# LightLinkV2.net
KiCad netlist of a schematic drawn in Altium Designer
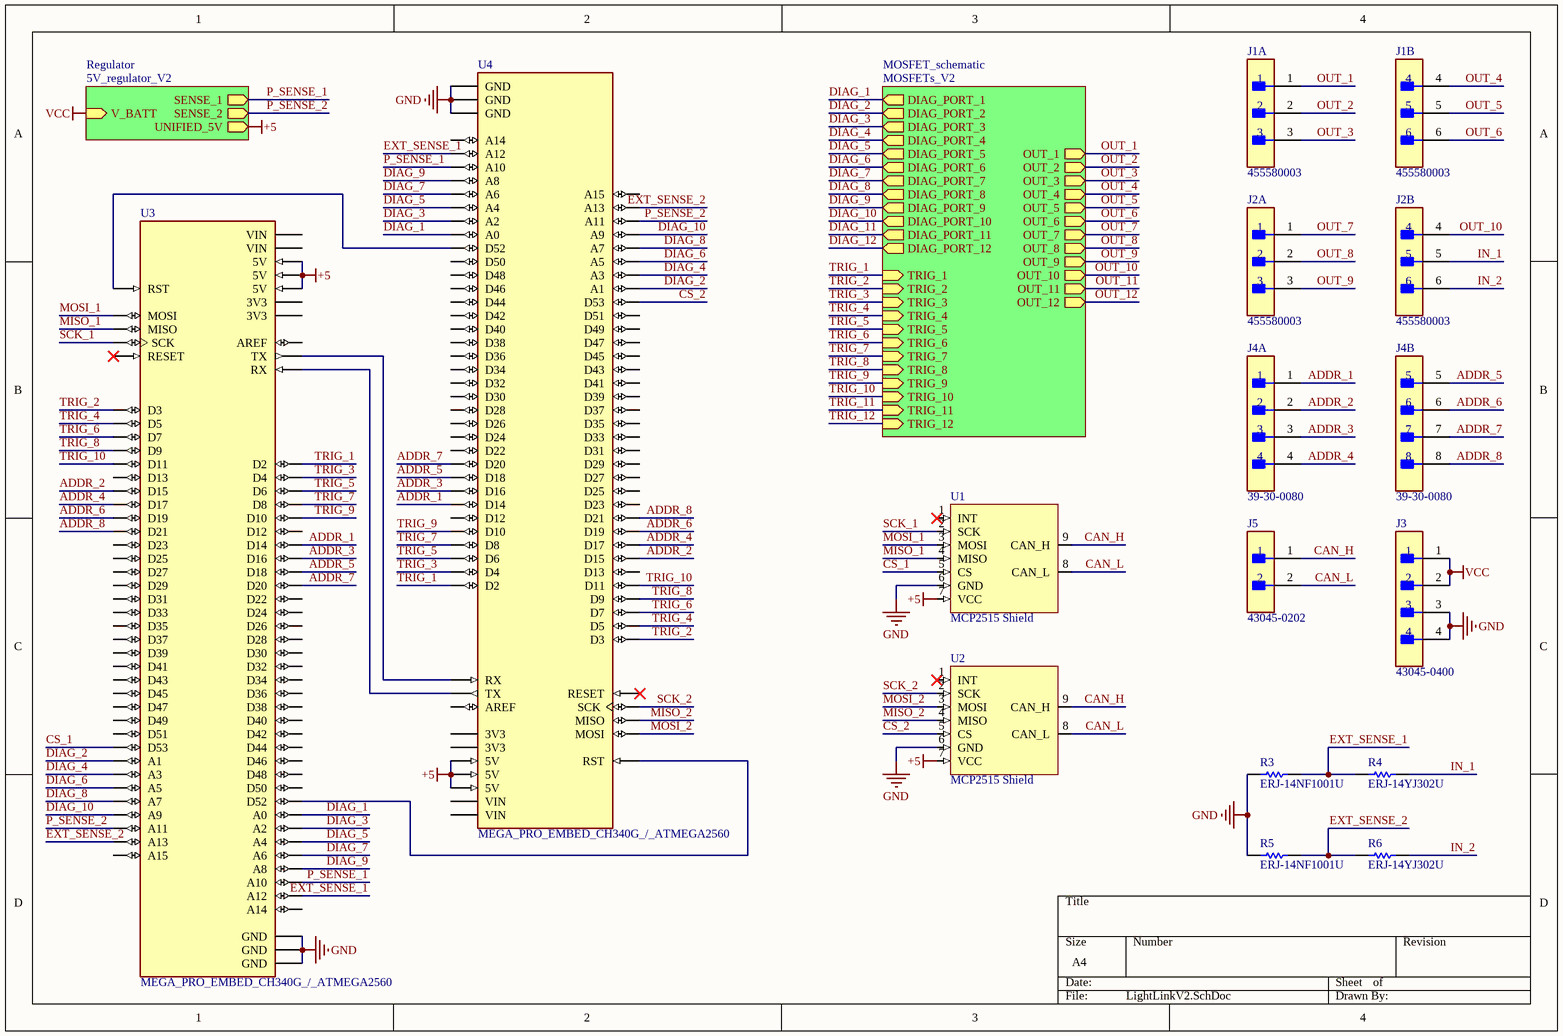
[diagram p0: LightLinkV2.SchDoc]

(export (version "E")
  (design (tool "Eeschema 10.0.6"))
  (components
    (comp (ref "J1")
      (value "455580003")
      (footprint "FP-455580003-MFG")
      (description "CONN HEADER R/A 6POS 4.2MM")
      (fields
        (field (name "OCTOPART") "https://octopart.com/45558-0003-molex-7672845")
        (field (name "MANUFACTURER") "Molex")
      )
      (libsource (lib "Altium Content Vault") (part "bb9cbdb24149a20ba329b4e86909569"))
    )
    (comp (ref "J2")
      (value "455580003")
      (footprint "FP-455580003-MFG")
      (description "CONN HEADER R/A 6POS 4.2MM")
      (fields
        (field (name "OCTOPART") "https://octopart.com/45558-0003-molex-7672845")
        (field (name "MANUFACTURER") "Molex")
      )
      (libsource (lib "Altium Content Vault") (part "bb9cbdb24149a20ba329b4e86909569"))
    )
    (comp (ref "J3")
      (value "43045-0400")
      (footprint "FP-43045-0400-MFG")
      (description "CONN HEADER R/A 4POS 3MM")
      (fields
        (field (name "MANUFACTURER") "Molex")
        (field (name "OCTOPART") "https://octopart.com/43045-0400-molex-287063")
      )
      (libsource (lib "Altium Content Vault") (part "c01754ab0efc13afb7424b896f394ef"))
    )
    (comp (ref "J4")
      (value "39-30-0080")
      (footprint "FP-39-30-0080-MFG")
      (description "CONN HEADER R/A 8POS 4.2MM")
      (libsource (lib "Altium Content Vault") (part "85438c39ca9ef07d43bb2e97c52bc44"))
    )
    (comp (ref "J5")
      (value "43045-0202")
      (footprint "FP-43045-0202-MFG")
      (description "CONN HEADER R/A 2POS")
      (libsource (lib "Altium Content Vault") (part "3bc925449376181038e59eaffc5286c"))
    )
    (comp (ref "R3")
      (value "ERJ-14NF1001U")
      (footprint "RESC3225X70X50NL20T20")
      (fields (field (name "MANUFACTURER") "Panasonic"))
      (libsource (lib "Altium Content Vault") (part "RES"))
    )
    (comp (ref "R4")
      (value "ERJ-14YJ302U")
      (footprint "RESC3225X70X50NL20T20")
      (fields (field (name "MANUFACTURER") "Panasonic"))
      (libsource (lib "Altium Content Vault") (part "RES"))
    )
    (comp (ref "R5")
      (value "ERJ-14NF1001U")
      (footprint "RESC3225X70X50NL20T20")
      (fields (field (name "MANUFACTURER") "Panasonic"))
      (libsource (lib "Altium Content Vault") (part "RES"))
    )
    (comp (ref "R6")
      (value "ERJ-14YJ302U")
      (footprint "RESC3225X70X50NL20T20")
      (fields (field (name "MANUFACTURER") "Panasonic"))
      (libsource (lib "Altium Content Vault") (part "RES"))
    )
    (comp (ref "U1")
      (value "MCP2515 Shield")
      (footprint "MCP2515 Shield-Footprint-1")
      (libsource (lib "uORocketry Hardware") (part "MCP2515 Shield Symbol"))
    )
    (comp (ref "U2")
      (value "MCP2515 Shield")
      (footprint "MCP2515 Shield-Footprint-1")
      (libsource (lib "uORocketry Hardware") (part "MCP2515 Shield Symbol"))
    )
    (comp (ref "U3")
      (value "MEGA_PRO_EMBED_CH340G_/_ATMEGA2560")
      (footprint "MODULE_MEGA_PRO_EMBED_CH340G_/_ATMEGA2560")
      (description "Mega 2560 PRO (Embed) CH340G/ATmega2560-16AU")
      (libsource (lib "") (part "MEGA_PRO_EMBED_CH340G_/_ATMEGA2560_1"))
    )
    (comp (ref "U4")
      (value "MEGA_PRO_EMBED_CH340G_/_ATMEGA2560")
      (footprint "MODULE_MEGA_PRO_EMBED_CH340G_/_ATMEGA2560")
      (description "Mega 2560 PRO (Embed) CH340G/ATmega2560-16AU")
      (libsource (lib "uORocketry Hardware") (part "MEGA_PRO_EMBED_CH340G_/_ATMEGA2560"))
    )
  )
  (nets
    (net (code "1") (name "+5") (class "Default")
      (node (ref "U1") (pin "7") (pinfunction "VCC_7") (pintype "input"))
      (node (ref "U2") (pin "7") (pinfunction "VCC_7") (pintype "input"))
      (node (ref "U3") (pin "5V_1") (pinfunction "5V_5V_1") (pintype "input"))
      (node (ref "U3") (pin "5V_2") (pinfunction "5V_5V_2") (pintype "input"))
      (node (ref "U3") (pin "5V_3") (pinfunction "5V_5V_3") (pintype "input"))
      (node (ref "U4") (pin "5V_1") (pinfunction "5V_5V_1") (pintype "input"))
      (node (ref "U4") (pin "5V_2") (pinfunction "5V_5V_2") (pintype "input"))
      (node (ref "U4") (pin "5V_3") (pinfunction "5V_5V_3") (pintype "input"))
    )
    (net (code "2") (name "/ADDR_1") (class "Default")
      (node (ref "J4") (pin "1") (pinfunction "1_1") (pintype "passive"))
      (node (ref "U3") (pin "D14") (pinfunction "D14_D14") (pintype "bidirectional"))
      (node (ref "U4") (pin "D14") (pinfunction "D14_D14") (pintype "bidirectional"))
    )
    (net (code "3") (name "/ADDR_2") (class "Default")
      (node (ref "J4") (pin "2") (pinfunction "2_2") (pintype "passive"))
      (node (ref "U3") (pin "D15") (pinfunction "D15_D15") (pintype "bidirectional"))
      (node (ref "U4") (pin "D15") (pinfunction "D15_D15") (pintype "bidirectional"))
    )
    (net (code "4") (name "/ADDR_3") (class "Default")
      (node (ref "J4") (pin "3") (pinfunction "3_3") (pintype "passive"))
      (node (ref "U3") (pin "D16") (pinfunction "D16_D16") (pintype "bidirectional"))
      (node (ref "U4") (pin "D16") (pinfunction "D16_D16") (pintype "bidirectional"))
    )
    (net (code "5") (name "/ADDR_4") (class "Default")
      (node (ref "J4") (pin "4") (pinfunction "4_4") (pintype "passive"))
      (node (ref "U3") (pin "D17") (pinfunction "D17_D17") (pintype "bidirectional"))
      (node (ref "U4") (pin "D17") (pinfunction "D17_D17") (pintype "bidirectional"))
    )
    (net (code "6") (name "/ADDR_5") (class "Default")
      (node (ref "J4") (pin "5") (pinfunction "5_5") (pintype "passive"))
      (node (ref "U3") (pin "D18") (pinfunction "D18_D18") (pintype "bidirectional"))
      (node (ref "U4") (pin "D18") (pinfunction "D18_D18") (pintype "bidirectional"))
    )
    (net (code "7") (name "/ADDR_6") (class "Default")
      (node (ref "J4") (pin "6") (pinfunction "6_6") (pintype "passive"))
      (node (ref "U3") (pin "D19") (pinfunction "D19_D19") (pintype "bidirectional"))
      (node (ref "U4") (pin "D19") (pinfunction "D19_D19") (pintype "bidirectional"))
    )
    (net (code "8") (name "/ADDR_7") (class "Default")
      (node (ref "J4") (pin "7") (pinfunction "7_7") (pintype "passive"))
      (node (ref "U3") (pin "D20") (pinfunction "D20_D20") (pintype "bidirectional"))
      (node (ref "U4") (pin "D20") (pinfunction "D20_D20") (pintype "bidirectional"))
    )
    (net (code "9") (name "/ADDR_8") (class "Default")
      (node (ref "J4") (pin "8") (pinfunction "8_8") (pintype "passive"))
      (node (ref "U3") (pin "D21") (pinfunction "D21_D21") (pintype "bidirectional"))
      (node (ref "U4") (pin "D21") (pinfunction "D21_D21") (pintype "bidirectional"))
    )
    (net (code "10") (name "/CAN_H") (class "Default")
      (node (ref "J5") (pin "1") (pinfunction "1_1") (pintype "passive"))
      (node (ref "U1") (pin "9") (pinfunction "CAN_H_9") (pintype "bidirectional"))
      (node (ref "U2") (pin "9") (pinfunction "CAN_H_9") (pintype "bidirectional"))
    )
    (net (code "11") (name "/CAN_L") (class "Default")
      (node (ref "J5") (pin "2") (pinfunction "2_2") (pintype "passive"))
      (node (ref "U1") (pin "8") (pinfunction "CAN_L_8") (pintype "bidirectional"))
      (node (ref "U2") (pin "8") (pinfunction "CAN_L_8") (pintype "bidirectional"))
    )
    (net (code "12") (name "/CS_1") (class "Default")
      (node (ref "U1") (pin "5") (pinfunction "CS_5") (pintype "input"))
      (node (ref "U3") (pin "D53") (pinfunction "D53_D53") (pintype "bidirectional"))
    )
    (net (code "13") (name "/CS_2") (class "Default")
      (node (ref "U2") (pin "5") (pinfunction "CS_5") (pintype "input"))
      (node (ref "U4") (pin "D53") (pinfunction "D53_D53") (pintype "bidirectional"))
    )
    (net (code "14") (name "/DIAG_1") (class "Default")
      (node (ref "U3") (pin "A0") (pinfunction "A0_A0") (pintype "bidirectional"))
      (node (ref "U4") (pin "A0") (pinfunction "A0_A0") (pintype "bidirectional"))
    )
    (net (code "15") (name "/DIAG_2") (class "Default")
      (node (ref "U3") (pin "A1") (pinfunction "A1_A1") (pintype "bidirectional"))
      (node (ref "U4") (pin "A1") (pinfunction "A1_A1") (pintype "bidirectional"))
    )
    (net (code "16") (name "/DIAG_3") (class "Default")
      (node (ref "U3") (pin "A2") (pinfunction "A2_A2") (pintype "bidirectional"))
      (node (ref "U4") (pin "A2") (pinfunction "A2_A2") (pintype "bidirectional"))
    )
    (net (code "17") (name "/DIAG_4") (class "Default")
      (node (ref "U3") (pin "A3") (pinfunction "A3_A3") (pintype "bidirectional"))
      (node (ref "U4") (pin "A3") (pinfunction "A3_A3") (pintype "bidirectional"))
    )
    (net (code "18") (name "/DIAG_5") (class "Default")
      (node (ref "U3") (pin "A4") (pinfunction "A4_A4") (pintype "bidirectional"))
      (node (ref "U4") (pin "A4") (pinfunction "A4_A4") (pintype "bidirectional"))
    )
    (net (code "19") (name "/DIAG_6") (class "Default")
      (node (ref "U3") (pin "A5") (pinfunction "A5_A5") (pintype "bidirectional"))
      (node (ref "U4") (pin "A5") (pinfunction "A5_A5") (pintype "bidirectional"))
    )
    (net (code "20") (name "/DIAG_7") (class "Default")
      (node (ref "U3") (pin "A6") (pinfunction "A6_A6") (pintype "bidirectional"))
      (node (ref "U4") (pin "A6") (pinfunction "A6_A6") (pintype "bidirectional"))
    )
    (net (code "21") (name "/DIAG_8") (class "Default")
      (node (ref "U3") (pin "A7") (pinfunction "A7_A7") (pintype "bidirectional"))
      (node (ref "U4") (pin "A7") (pinfunction "A7_A7") (pintype "bidirectional"))
    )
    (net (code "22") (name "/DIAG_9") (class "Default")
      (node (ref "U3") (pin "A8") (pinfunction "A8_A8") (pintype "bidirectional"))
      (node (ref "U4") (pin "A8") (pinfunction "A8_A8") (pintype "bidirectional"))
    )
    (net (code "23") (name "/DIAG_10") (class "Default")
      (node (ref "U3") (pin "A9") (pinfunction "A9_A9") (pintype "bidirectional"))
      (node (ref "U4") (pin "A9") (pinfunction "A9_A9") (pintype "bidirectional"))
    )
    (net (code "26") (name "/EXT_SENSE_1") (class "Default")
      (node (ref "R3") (pin "2") (pinfunction "2_2") (pintype "passive"))
      (node (ref "R4") (pin "1") (pinfunction "1_1") (pintype "passive"))
      (node (ref "U3") (pin "A12") (pinfunction "A12_A12") (pintype "bidirectional"))
      (node (ref "U4") (pin "A12") (pinfunction "A12_A12") (pintype "bidirectional"))
    )
    (net (code "27") (name "/EXT_SENSE_2") (class "Default")
      (node (ref "R5") (pin "2") (pinfunction "2_2") (pintype "passive"))
      (node (ref "R6") (pin "1") (pinfunction "1_1") (pintype "passive"))
      (node (ref "U3") (pin "A13") (pinfunction "A13_A13") (pintype "bidirectional"))
      (node (ref "U4") (pin "A13") (pinfunction "A13_A13") (pintype "bidirectional"))
    )
    (net (code "28") (name "/IN_1") (class "Default")
      (node (ref "J2") (pin "5") (pinfunction "5_5") (pintype "passive"))
      (node (ref "R4") (pin "2") (pinfunction "2_2") (pintype "passive"))
    )
    (net (code "29") (name "/IN_2") (class "Default")
      (node (ref "J2") (pin "6") (pinfunction "6_6") (pintype "passive"))
      (node (ref "R6") (pin "2") (pinfunction "2_2") (pintype "passive"))
    )
    (net (code "30") (name "/MISO_1") (class "Default")
      (node (ref "U1") (pin "4") (pinfunction "MISO_4") (pintype "input"))
      (node (ref "U3") (pin "MISO") (pinfunction "MISO_MISO") (pintype "bidirectional"))
    )
    (net (code "31") (name "/MISO_2") (class "Default")
      (node (ref "U2") (pin "4") (pinfunction "MISO_4") (pintype "input"))
      (node (ref "U4") (pin "MISO") (pinfunction "MISO_MISO") (pintype "bidirectional"))
    )
    (net (code "32") (name "/MOSI_1") (class "Default")
      (node (ref "U1") (pin "3") (pinfunction "MOSI_3") (pintype "input"))
      (node (ref "U3") (pin "MOSI") (pinfunction "MOSI_MOSI") (pintype "bidirectional"))
    )
    (net (code "33") (name "/MOSI_2") (class "Default")
      (node (ref "U2") (pin "3") (pinfunction "MOSI_3") (pintype "input"))
      (node (ref "U4") (pin "MOSI") (pinfunction "MOSI_MOSI") (pintype "bidirectional"))
    )
    (net (code "34") (name "/OUT_1") (class "Default")
      (node (ref "J1") (pin "1") (pinfunction "1_1") (pintype "passive"))
    )
    (net (code "35") (name "/OUT_2") (class "Default")
      (node (ref "J1") (pin "2") (pinfunction "2_2") (pintype "passive"))
    )
    (net (code "36") (name "/OUT_3") (class "Default")
      (node (ref "J1") (pin "3") (pinfunction "3_3") (pintype "passive"))
    )
    (net (code "37") (name "/OUT_4") (class "Default")
      (node (ref "J1") (pin "4") (pinfunction "4_4") (pintype "passive"))
    )
    (net (code "38") (name "/OUT_5") (class "Default")
      (node (ref "J1") (pin "5") (pinfunction "5_5") (pintype "passive"))
    )
    (net (code "39") (name "/OUT_6") (class "Default")
      (node (ref "J1") (pin "6") (pinfunction "6_6") (pintype "passive"))
    )
    (net (code "40") (name "/OUT_7") (class "Default")
      (node (ref "J2") (pin "1") (pinfunction "1_1") (pintype "passive"))
    )
    (net (code "41") (name "/OUT_8") (class "Default")
      (node (ref "J2") (pin "2") (pinfunction "2_2") (pintype "passive"))
    )
    (net (code "42") (name "/OUT_9") (class "Default")
      (node (ref "J2") (pin "3") (pinfunction "3_3") (pintype "passive"))
    )
    (net (code "43") (name "/OUT_10") (class "Default")
      (node (ref "J2") (pin "4") (pinfunction "4_4") (pintype "passive"))
    )
    (net (code "46") (name "/P_SENSE_1") (class "Default")
      (node (ref "U3") (pin "A10") (pinfunction "A10_A10") (pintype "bidirectional"))
      (node (ref "U4") (pin "A10") (pinfunction "A10_A10") (pintype "bidirectional"))
    )
    (net (code "47") (name "/P_SENSE_2") (class "Default")
      (node (ref "U3") (pin "A11") (pinfunction "A11_A11") (pintype "bidirectional"))
      (node (ref "U4") (pin "A11") (pinfunction "A11_A11") (pintype "bidirectional"))
    )
    (net (code "48") (name "/SCK_1") (class "Default")
      (node (ref "U1") (pin "2") (pinfunction "SCK_2") (pintype "input"))
      (node (ref "U3") (pin "SCK") (pinfunction "SCK_SCK") (pintype "bidirectional"))
    )
    (net (code "49") (name "/SCK_2") (class "Default")
      (node (ref "U2") (pin "2") (pinfunction "SCK_2") (pintype "input"))
      (node (ref "U4") (pin "SCK") (pinfunction "SCK_SCK") (pintype "bidirectional"))
    )
    (net (code "50") (name "/TRIG_1") (class "Default")
      (node (ref "U3") (pin "D2") (pinfunction "D2_D2") (pintype "bidirectional"))
      (node (ref "U4") (pin "D2") (pinfunction "D2_D2") (pintype "bidirectional"))
    )
    (net (code "51") (name "/TRIG_2") (class "Default")
      (node (ref "U3") (pin "D3") (pinfunction "D3_D3") (pintype "bidirectional"))
      (node (ref "U4") (pin "D3") (pinfunction "D3_D3") (pintype "bidirectional"))
    )
    (net (code "52") (name "/TRIG_3") (class "Default")
      (node (ref "U3") (pin "D4") (pinfunction "D4_D4") (pintype "bidirectional"))
      (node (ref "U4") (pin "D4") (pinfunction "D4_D4") (pintype "bidirectional"))
    )
    (net (code "53") (name "/TRIG_4") (class "Default")
      (node (ref "U3") (pin "D5") (pinfunction "D5_D5") (pintype "bidirectional"))
      (node (ref "U4") (pin "D5") (pinfunction "D5_D5") (pintype "bidirectional"))
    )
    (net (code "54") (name "/TRIG_5") (class "Default")
      (node (ref "U3") (pin "D6") (pinfunction "D6_D6") (pintype "bidirectional"))
      (node (ref "U4") (pin "D6") (pinfunction "D6_D6") (pintype "bidirectional"))
    )
    (net (code "55") (name "/TRIG_6") (class "Default")
      (node (ref "U3") (pin "D7") (pinfunction "D7_D7") (pintype "bidirectional"))
      (node (ref "U4") (pin "D7") (pinfunction "D7_D7") (pintype "bidirectional"))
    )
    (net (code "56") (name "/TRIG_7") (class "Default")
      (node (ref "U3") (pin "D8") (pinfunction "D8_D8") (pintype "bidirectional"))
      (node (ref "U4") (pin "D8") (pinfunction "D8_D8") (pintype "bidirectional"))
    )
    (net (code "57") (name "/TRIG_8") (class "Default")
      (node (ref "U3") (pin "D9") (pinfunction "D9_D9") (pintype "bidirectional"))
      (node (ref "U4") (pin "D9") (pinfunction "D9_D9") (pintype "bidirectional"))
    )
    (net (code "58") (name "/TRIG_9") (class "Default")
      (node (ref "U3") (pin "D10") (pinfunction "D10_D10") (pintype "bidirectional"))
      (node (ref "U4") (pin "D10") (pinfunction "D10_D10") (pintype "bidirectional"))
    )
    (net (code "59") (name "/TRIG_10") (class "Default")
      (node (ref "U3") (pin "D11") (pinfunction "D11_D11") (pintype "bidirectional"))
      (node (ref "U4") (pin "D11") (pinfunction "D11_D11") (pintype "bidirectional"))
    )
    (net (code "62") (name "GND") (class "Default")
      (node (ref "J3") (pin "3") (pinfunction "3_3") (pintype "passive"))
      (node (ref "J3") (pin "4") (pinfunction "4_4") (pintype "passive"))
      (node (ref "R3") (pin "1") (pinfunction "1_1") (pintype "passive"))
      (node (ref "R5") (pin "1") (pinfunction "1_1") (pintype "passive"))
      (node (ref "U1") (pin "6") (pinfunction "GND_6") (pintype "input"))
      (node (ref "U2") (pin "6") (pinfunction "GND_6") (pintype "input"))
      (node (ref "U3") (pin "GND_1") (pinfunction "GND_GND_1") (pintype "power_in"))
      (node (ref "U3") (pin "GND_2") (pinfunction "GND_GND_2") (pintype "power_in"))
      (node (ref "U3") (pin "GND_3") (pinfunction "GND_GND_3") (pintype "power_in"))
      (node (ref "U4") (pin "GND_1") (pinfunction "GND_GND_1") (pintype "power_in"))
      (node (ref "U4") (pin "GND_2") (pinfunction "GND_GND_2") (pintype "power_in"))
      (node (ref "U4") (pin "GND_3") (pinfunction "GND_GND_3") (pintype "power_in"))
    )
    (net (code "63") (name "Net-(U3-PadD52)") (class "Default")
      (node (ref "U3") (pin "D52") (pinfunction "D52_D52") (pintype "bidirectional"))
      (node (ref "U4") (pin "RST") (pinfunction "RST_RST") (pintype "input"))
    )
    (net (code "64") (name "Net-(U3-PadRST)") (class "Default")
      (node (ref "U3") (pin "RST") (pinfunction "RST_RST") (pintype "input"))
      (node (ref "U4") (pin "D52") (pinfunction "D52_D52") (pintype "bidirectional"))
    )
    (net (code "65") (name "Net-(U3-PadRX)") (class "Default")
      (node (ref "U3") (pin "RX") (pinfunction "RX_RX") (pintype "input"))
      (node (ref "U4") (pin "TX") (pinfunction "TX_TX") (pintype "output"))
    )
    (net (code "66") (name "Net-(U3-PadTX)") (class "Default")
      (node (ref "U3") (pin "TX") (pinfunction "TX_TX") (pintype "output"))
      (node (ref "U4") (pin "RX") (pinfunction "RX_RX") (pintype "input"))
    )
    (net (code "67") (name "VCC") (class "Default")
      (node (ref "J3") (pin "1") (pinfunction "1_1") (pintype "passive"))
      (node (ref "J3") (pin "2") (pinfunction "2_2") (pintype "passive"))
    )
    (net (code "68") (name "unconnected-(U1-INT-Pad1)") (class "Default")
      (node (ref "U1") (pin "1") (pinfunction "INT_1") (pintype "input+no_connect"))
    )
    (net (code "69") (name "unconnected-(U2-INT-Pad1)") (class "Default")
      (node (ref "U2") (pin "1") (pinfunction "INT_1") (pintype "input+no_connect"))
    )
    (net (code "70") (name "unconnected-(U3-3V3-Pad3V3_1)") (class "Default")
      (node (ref "U3") (pin "3V3_1") (pinfunction "3V3_3V3_1") (pintype "power_in"))
    )
    (net (code "71") (name "unconnected-(U3-3V3-Pad3V3_2)") (class "Default")
      (node (ref "U3") (pin "3V3_2") (pinfunction "3V3_3V3_2") (pintype "power_in"))
    )
    (net (code "72") (name "unconnected-(U3-PadA14)") (class "Default")
      (node (ref "U3") (pin "A14") (pinfunction "A14_A14") (pintype "bidirectional"))
    )
    (net (code "73") (name "unconnected-(U3-PadA15)") (class "Default")
      (node (ref "U3") (pin "A15") (pinfunction "A15_A15") (pintype "bidirectional"))
    )
    (net (code "74") (name "unconnected-(U3-PadAREF)") (class "Default")
      (node (ref "U3") (pin "AREF") (pinfunction "AREF_AREF") (pintype "bidirectional"))
    )
    (net (code "75") (name "unconnected-(U3-PadD12)") (class "Default")
      (node (ref "U3") (pin "D12") (pinfunction "D12_D12") (pintype "bidirectional"))
    )
    (net (code "76") (name "unconnected-(U3-PadD13)") (class "Default")
      (node (ref "U3") (pin "D13") (pinfunction "D13_D13") (pintype "bidirectional"))
    )
    (net (code "77") (name "unconnected-(U3-PadD22)") (class "Default")
      (node (ref "U3") (pin "D22") (pinfunction "D22_D22") (pintype "bidirectional"))
    )
    (net (code "78") (name "unconnected-(U3-PadD23)") (class "Default")
      (node (ref "U3") (pin "D23") (pinfunction "D23_D23") (pintype "bidirectional"))
    )
    (net (code "79") (name "unconnected-(U3-PadD24)") (class "Default")
      (node (ref "U3") (pin "D24") (pinfunction "D24_D24") (pintype "bidirectional"))
    )
    (net (code "80") (name "unconnected-(U3-PadD25)") (class "Default")
      (node (ref "U3") (pin "D25") (pinfunction "D25_D25") (pintype "bidirectional"))
    )
    (net (code "81") (name "unconnected-(U3-PadD26)") (class "Default")
      (node (ref "U3") (pin "D26") (pinfunction "D26_D26") (pintype "bidirectional"))
    )
    (net (code "82") (name "unconnected-(U3-PadD27)") (class "Default")
      (node (ref "U3") (pin "D27") (pinfunction "D27_D27") (pintype "bidirectional"))
    )
    (net (code "83") (name "unconnected-(U3-PadD28)") (class "Default")
      (node (ref "U3") (pin "D28") (pinfunction "D28_D28") (pintype "bidirectional"))
    )
    (net (code "84") (name "unconnected-(U3-PadD29)") (class "Default")
      (node (ref "U3") (pin "D29") (pinfunction "D29_D29") (pintype "bidirectional"))
    )
    (net (code "85") (name "unconnected-(U3-PadD30)") (class "Default")
      (node (ref "U3") (pin "D30") (pinfunction "D30_D30") (pintype "bidirectional"))
    )
    (net (code "86") (name "unconnected-(U3-PadD31)") (class "Default")
      (node (ref "U3") (pin "D31") (pinfunction "D31_D31") (pintype "bidirectional"))
    )
    (net (code "87") (name "unconnected-(U3-PadD32)") (class "Default")
      (node (ref "U3") (pin "D32") (pinfunction "D32_D32") (pintype "bidirectional"))
    )
    (net (code "88") (name "unconnected-(U3-PadD33)") (class "Default")
      (node (ref "U3") (pin "D33") (pinfunction "D33_D33") (pintype "bidirectional"))
    )
    (net (code "89") (name "unconnected-(U3-PadD34)") (class "Default")
      (node (ref "U3") (pin "D34") (pinfunction "D34_D34") (pintype "bidirectional"))
    )
    (net (code "90") (name "unconnected-(U3-PadD35)") (class "Default")
      (node (ref "U3") (pin "D35") (pinfunction "D35_D35") (pintype "bidirectional"))
    )
    (net (code "91") (name "unconnected-(U3-PadD36)") (class "Default")
      (node (ref "U3") (pin "D36") (pinfunction "D36_D36") (pintype "bidirectional"))
    )
    (net (code "92") (name "unconnected-(U3-PadD37)") (class "Default")
      (node (ref "U3") (pin "D37") (pinfunction "D37_D37") (pintype "bidirectional"))
    )
    (net (code "93") (name "unconnected-(U3-PadD38)") (class "Default")
      (node (ref "U3") (pin "D38") (pinfunction "D38_D38") (pintype "bidirectional"))
    )
    (net (code "94") (name "unconnected-(U3-PadD39)") (class "Default")
      (node (ref "U3") (pin "D39") (pinfunction "D39_D39") (pintype "bidirectional"))
    )
    (net (code "95") (name "unconnected-(U3-PadD40)") (class "Default")
      (node (ref "U3") (pin "D40") (pinfunction "D40_D40") (pintype "bidirectional"))
    )
    (net (code "96") (name "unconnected-(U3-PadD41)") (class "Default")
      (node (ref "U3") (pin "D41") (pinfunction "D41_D41") (pintype "bidirectional"))
    )
    (net (code "97") (name "unconnected-(U3-PadD42)") (class "Default")
      (node (ref "U3") (pin "D42") (pinfunction "D42_D42") (pintype "bidirectional"))
    )
    (net (code "98") (name "unconnected-(U3-PadD43)") (class "Default")
      (node (ref "U3") (pin "D43") (pinfunction "D43_D43") (pintype "bidirectional"))
    )
    (net (code "99") (name "unconnected-(U3-PadD44)") (class "Default")
      (node (ref "U3") (pin "D44") (pinfunction "D44_D44") (pintype "bidirectional"))
    )
    (net (code "100") (name "unconnected-(U3-PadD45)") (class "Default")
      (node (ref "U3") (pin "D45") (pinfunction "D45_D45") (pintype "bidirectional"))
    )
    (net (code "101") (name "unconnected-(U3-PadD46)") (class "Default")
      (node (ref "U3") (pin "D46") (pinfunction "D46_D46") (pintype "bidirectional"))
    )
    (net (code "102") (name "unconnected-(U3-PadD47)") (class "Default")
      (node (ref "U3") (pin "D47") (pinfunction "D47_D47") (pintype "bidirectional"))
    )
    (net (code "103") (name "unconnected-(U3-PadD48)") (class "Default")
      (node (ref "U3") (pin "D48") (pinfunction "D48_D48") (pintype "bidirectional"))
    )
    (net (code "104") (name "unconnected-(U3-PadD49)") (class "Default")
      (node (ref "U3") (pin "D49") (pinfunction "D49_D49") (pintype "bidirectional"))
    )
    (net (code "105") (name "unconnected-(U3-PadD50)") (class "Default")
      (node (ref "U3") (pin "D50") (pinfunction "D50_D50") (pintype "bidirectional"))
    )
    (net (code "106") (name "unconnected-(U3-PadD51)") (class "Default")
      (node (ref "U3") (pin "D51") (pinfunction "D51_D51") (pintype "bidirectional"))
    )
    (net (code "107") (name "unconnected-(U3-PadRESET)") (class "Default")
      (node (ref "U3") (pin "RESET") (pinfunction "RESET_RESET") (pintype "input+no_connect"))
    )
    (net (code "108") (name "unconnected-(U3-VIN-PadVIN_1)") (class "Default")
      (node (ref "U3") (pin "VIN_1") (pinfunction "VIN_VIN_1") (pintype "power_in"))
    )
    (net (code "109") (name "unconnected-(U3-VIN-PadVIN_2)") (class "Default")
      (node (ref "U3") (pin "VIN_2") (pinfunction "VIN_VIN_2") (pintype "power_in"))
    )
    (net (code "110") (name "unconnected-(U4-3V3-Pad3V3_1)") (class "Default")
      (node (ref "U4") (pin "3V3_1") (pinfunction "3V3_3V3_1") (pintype "power_in"))
    )
    (net (code "111") (name "unconnected-(U4-3V3-Pad3V3_2)") (class "Default")
      (node (ref "U4") (pin "3V3_2") (pinfunction "3V3_3V3_2") (pintype "power_in"))
    )
    (net (code "112") (name "unconnected-(U4-PadA14)") (class "Default")
      (node (ref "U4") (pin "A14") (pinfunction "A14_A14") (pintype "bidirectional"))
    )
    (net (code "113") (name "unconnected-(U4-PadA15)") (class "Default")
      (node (ref "U4") (pin "A15") (pinfunction "A15_A15") (pintype "bidirectional"))
    )
    (net (code "114") (name "unconnected-(U4-PadAREF)") (class "Default")
      (node (ref "U4") (pin "AREF") (pinfunction "AREF_AREF") (pintype "bidirectional"))
    )
    (net (code "115") (name "unconnected-(U4-PadD12)") (class "Default")
      (node (ref "U4") (pin "D12") (pinfunction "D12_D12") (pintype "bidirectional"))
    )
    (net (code "116") (name "unconnected-(U4-PadD13)") (class "Default")
      (node (ref "U4") (pin "D13") (pinfunction "D13_D13") (pintype "bidirectional"))
    )
    (net (code "117") (name "unconnected-(U4-PadD22)") (class "Default")
      (node (ref "U4") (pin "D22") (pinfunction "D22_D22") (pintype "bidirectional"))
    )
    (net (code "118") (name "unconnected-(U4-PadD23)") (class "Default")
      (node (ref "U4") (pin "D23") (pinfunction "D23_D23") (pintype "bidirectional"))
    )
    (net (code "119") (name "unconnected-(U4-PadD24)") (class "Default")
      (node (ref "U4") (pin "D24") (pinfunction "D24_D24") (pintype "bidirectional"))
    )
    (net (code "120") (name "unconnected-(U4-PadD25)") (class "Default")
      (node (ref "U4") (pin "D25") (pinfunction "D25_D25") (pintype "bidirectional"))
    )
    (net (code "121") (name "unconnected-(U4-PadD26)") (class "Default")
      (node (ref "U4") (pin "D26") (pinfunction "D26_D26") (pintype "bidirectional"))
    )
    (net (code "122") (name "unconnected-(U4-PadD27)") (class "Default")
      (node (ref "U4") (pin "D27") (pinfunction "D27_D27") (pintype "bidirectional"))
    )
    (net (code "123") (name "unconnected-(U4-PadD28)") (class "Default")
      (node (ref "U4") (pin "D28") (pinfunction "D28_D28") (pintype "bidirectional"))
    )
    (net (code "124") (name "unconnected-(U4-PadD29)") (class "Default")
      (node (ref "U4") (pin "D29") (pinfunction "D29_D29") (pintype "bidirectional"))
    )
    (net (code "125") (name "unconnected-(U4-PadD30)") (class "Default")
      (node (ref "U4") (pin "D30") (pinfunction "D30_D30") (pintype "bidirectional"))
    )
    (net (code "126") (name "unconnected-(U4-PadD31)") (class "Default")
      (node (ref "U4") (pin "D31") (pinfunction "D31_D31") (pintype "bidirectional"))
    )
    (net (code "127") (name "unconnected-(U4-PadD32)") (class "Default")
      (node (ref "U4") (pin "D32") (pinfunction "D32_D32") (pintype "bidirectional"))
    )
    (net (code "128") (name "unconnected-(U4-PadD33)") (class "Default")
      (node (ref "U4") (pin "D33") (pinfunction "D33_D33") (pintype "bidirectional"))
    )
    (net (code "129") (name "unconnected-(U4-PadD34)") (class "Default")
      (node (ref "U4") (pin "D34") (pinfunction "D34_D34") (pintype "bidirectional"))
    )
    (net (code "130") (name "unconnected-(U4-PadD35)") (class "Default")
      (node (ref "U4") (pin "D35") (pinfunction "D35_D35") (pintype "bidirectional"))
    )
    (net (code "131") (name "unconnected-(U4-PadD36)") (class "Default")
      (node (ref "U4") (pin "D36") (pinfunction "D36_D36") (pintype "bidirectional"))
    )
    (net (code "132") (name "unconnected-(U4-PadD37)") (class "Default")
      (node (ref "U4") (pin "D37") (pinfunction "D37_D37") (pintype "bidirectional"))
    )
    (net (code "133") (name "unconnected-(U4-PadD38)") (class "Default")
      (node (ref "U4") (pin "D38") (pinfunction "D38_D38") (pintype "bidirectional"))
    )
    (net (code "134") (name "unconnected-(U4-PadD39)") (class "Default")
      (node (ref "U4") (pin "D39") (pinfunction "D39_D39") (pintype "bidirectional"))
    )
    (net (code "135") (name "unconnected-(U4-PadD40)") (class "Default")
      (node (ref "U4") (pin "D40") (pinfunction "D40_D40") (pintype "bidirectional"))
    )
    (net (code "136") (name "unconnected-(U4-PadD41)") (class "Default")
      (node (ref "U4") (pin "D41") (pinfunction "D41_D41") (pintype "bidirectional"))
    )
    (net (code "137") (name "unconnected-(U4-PadD42)") (class "Default")
      (node (ref "U4") (pin "D42") (pinfunction "D42_D42") (pintype "bidirectional"))
    )
    (net (code "138") (name "unconnected-(U4-PadD43)") (class "Default")
      (node (ref "U4") (pin "D43") (pinfunction "D43_D43") (pintype "bidirectional"))
    )
    (net (code "139") (name "unconnected-(U4-PadD44)") (class "Default")
      (node (ref "U4") (pin "D44") (pinfunction "D44_D44") (pintype "bidirectional"))
    )
    (net (code "140") (name "unconnected-(U4-PadD45)") (class "Default")
      (node (ref "U4") (pin "D45") (pinfunction "D45_D45") (pintype "bidirectional"))
    )
    (net (code "141") (name "unconnected-(U4-PadD46)") (class "Default")
      (node (ref "U4") (pin "D46") (pinfunction "D46_D46") (pintype "bidirectional"))
    )
    (net (code "142") (name "unconnected-(U4-PadD47)") (class "Default")
      (node (ref "U4") (pin "D47") (pinfunction "D47_D47") (pintype "bidirectional"))
    )
    (net (code "143") (name "unconnected-(U4-PadD48)") (class "Default")
      (node (ref "U4") (pin "D48") (pinfunction "D48_D48") (pintype "bidirectional"))
    )
    (net (code "144") (name "unconnected-(U4-PadD49)") (class "Default")
      (node (ref "U4") (pin "D49") (pinfunction "D49_D49") (pintype "bidirectional"))
    )
    (net (code "145") (name "unconnected-(U4-PadD50)") (class "Default")
      (node (ref "U4") (pin "D50") (pinfunction "D50_D50") (pintype "bidirectional"))
    )
    (net (code "146") (name "unconnected-(U4-PadD51)") (class "Default")
      (node (ref "U4") (pin "D51") (pinfunction "D51_D51") (pintype "bidirectional"))
    )
    (net (code "147") (name "unconnected-(U4-PadRESET)") (class "Default")
      (node (ref "U4") (pin "RESET") (pinfunction "RESET_RESET") (pintype "input+no_connect"))
    )
    (net (code "148") (name "unconnected-(U4-VIN-PadVIN_1)") (class "Default")
      (node (ref "U4") (pin "VIN_1") (pinfunction "VIN_VIN_1") (pintype "power_in"))
    )
    (net (code "149") (name "unconnected-(U4-VIN-PadVIN_2)") (class "Default")
      (node (ref "U4") (pin "VIN_2") (pinfunction "VIN_VIN_2") (pintype "power_in"))
    )
  )
)
